# fan_control_module_0_9.net
KiCad netlist of a schematic drawn in EAGLE
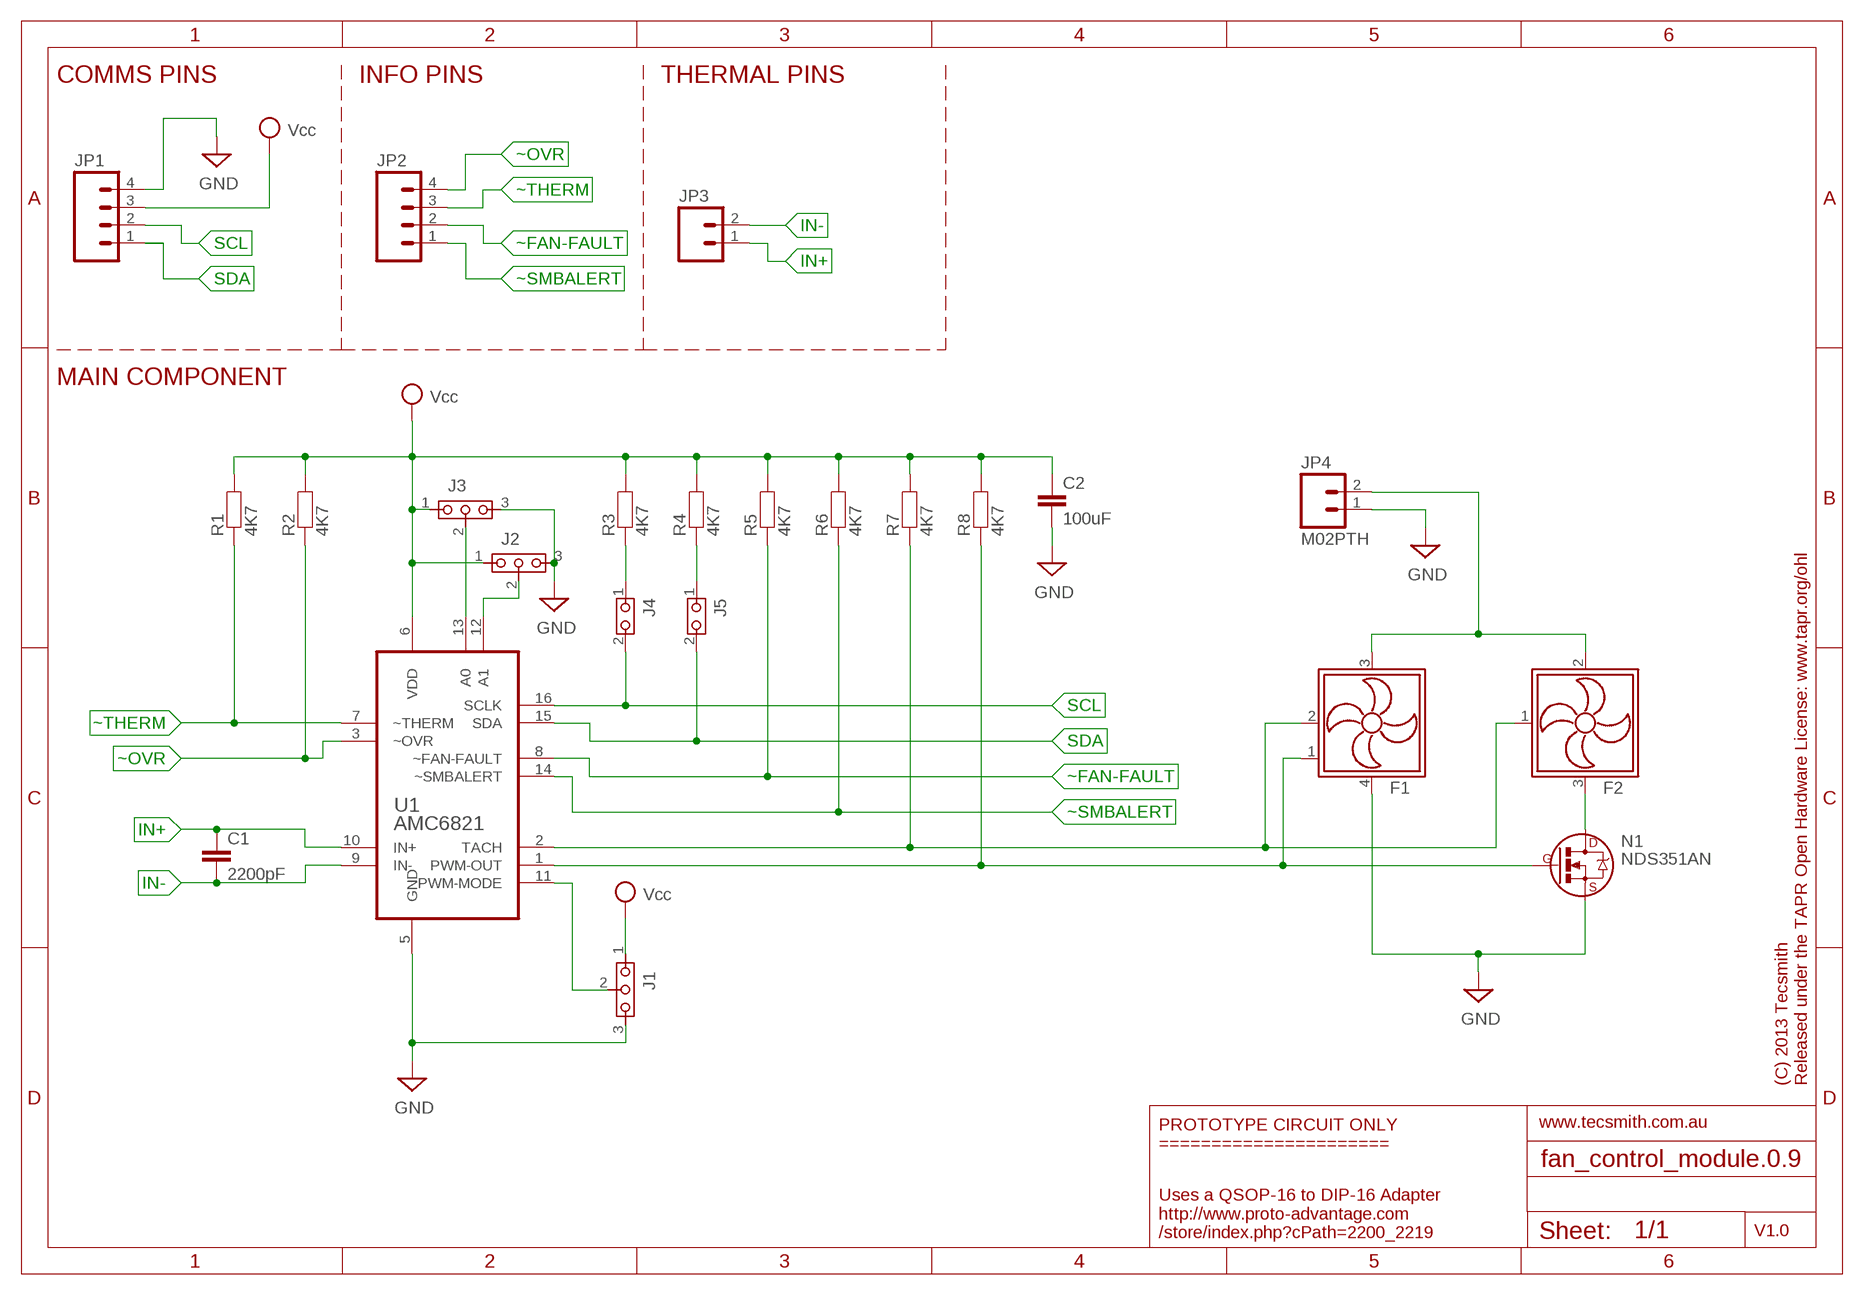
[diagram p0: schematic, sheet 1]

(export (version "E")
  (design (tool "Eeschema 10.0.6"))
  (components
    (comp (ref "C1")
      (value "2200pF")
      (footprint "eagle-import:0603")
      (libsource (lib "eagle-import") (part "CAP0603"))
    )
    (comp (ref "C2")
      (value "100uF")
      (footprint "eagle-import:0603")
      (libsource (lib "eagle-import") (part "CAP0603"))
    )
    (comp (ref "F1")
      (value "FAN_4-WIREINTEL")
      (footprint "eagle-import:47053-1000")
      (libsource (lib "eagle-import") (part "FAN_4-WIREINTEL"))
    )
    (comp (ref "F2")
      (value "FAN_3-WIRE")
      (footprint "eagle-import:22-23-2031")
      (libsource (lib "eagle-import") (part "FAN_3-WIRE"))
    )
    (comp (ref "J1")
      (value "SJ3SMD")
      (footprint "eagle-import:SJ2")
      (libsource (lib "eagle-import") (part "SJ3SMD"))
    )
    (comp (ref "J2")
      (value "SJ3SMD")
      (footprint "eagle-import:SJ2")
      (libsource (lib "eagle-import") (part "SJ3SMD"))
    )
    (comp (ref "J3")
      (value "SJ3SMD")
      (footprint "eagle-import:SJ2")
      (libsource (lib "eagle-import") (part "SJ3SMD"))
    )
    (comp (ref "J4")
      (value "SJSMD")
      (footprint "eagle-import:SJ")
      (libsource (lib "eagle-import") (part "SJSMD"))
    )
    (comp (ref "J5")
      (value "SJSMD")
      (footprint "eagle-import:SJ")
      (libsource (lib "eagle-import") (part "SJSMD"))
    )
    (comp (ref "JP1")
      (value "M04PTH")
      (footprint "eagle-import:1X04")
      (libsource (lib "eagle-import") (part "M04PTH"))
    )
    (comp (ref "JP2")
      (value "M04PTH")
      (footprint "eagle-import:1X04")
      (libsource (lib "eagle-import") (part "M04PTH"))
    )
    (comp (ref "JP3")
      (value "M02PTH")
      (footprint "eagle-import:1X02")
      (libsource (lib "eagle-import") (part "M02PTH"))
    )
    (comp (ref "JP4")
      (value "M02PTH")
      (footprint "eagle-import:1X02")
      (libsource (lib "eagle-import") (part "M02PTH"))
    )
    (comp (ref "N1")
      (value "NDS351AN")
      (footprint "eagle-import:SOT23")
      (libsource (lib "eagle-import") (part "NMOSFETGSD"))
    )
    (comp (ref "R1")
      (value "4K7")
      (footprint "eagle-import:0603")
      (libsource (lib "eagle-import") (part "RESISTOR0603"))
    )
    (comp (ref "R2")
      (value "4K7")
      (footprint "eagle-import:0603")
      (libsource (lib "eagle-import") (part "RESISTOR0603"))
    )
    (comp (ref "R3")
      (value "4K7")
      (footprint "eagle-import:0603")
      (libsource (lib "eagle-import") (part "RESISTOR0603"))
    )
    (comp (ref "R4")
      (value "4K7")
      (footprint "eagle-import:0603")
      (libsource (lib "eagle-import") (part "RESISTOR0603"))
    )
    (comp (ref "R5")
      (value "4K7")
      (footprint "eagle-import:0603")
      (libsource (lib "eagle-import") (part "RESISTOR0603"))
    )
    (comp (ref "R6")
      (value "4K7")
      (footprint "eagle-import:0603")
      (libsource (lib "eagle-import") (part "RESISTOR0603"))
    )
    (comp (ref "R7")
      (value "4K7")
      (footprint "eagle-import:0603")
      (libsource (lib "eagle-import") (part "RESISTOR0603"))
    )
    (comp (ref "R8")
      (value "4K7")
      (footprint "eagle-import:0603")
      (libsource (lib "eagle-import") (part "RESISTOR0603"))
    )
    (comp (ref "U1")
      (value "AMC6821")
      (footprint "eagle-import:QSOP-16N")
      (fields (field (name "MPN") "AMC6821SDBQ"))
      (libsource (lib "eagle-import") (part "AMC6821SDBQQSOP"))
    )
  )
  (nets
    (net (code "1") (name "/VFAN") (class "Default")
      (node (ref "F1") (pin "3") (pinfunction "PWR_3") (pintype "power_in"))
      (node (ref "F2") (pin "2") (pinfunction "PWR_2") (pintype "power_in"))
      (node (ref "JP4") (pin "2") (pinfunction "2_2") (pintype "passive"))
    )
    (net (code "2") (name "/~{FAN-FAULT}") (class "Default")
      (node (ref "JP2") (pin "2") (pinfunction "2_2") (pintype "passive"))
      (node (ref "R5") (pin "1") (pinfunction "1_1") (pintype "passive"))
      (node (ref "U1") (pin "8") (pinfunction "~{FAN-FAULT}_8") (pintype "output"))
    )
    (net (code "3") (name "/~{OVR}") (class "Default")
      (node (ref "JP2") (pin "4") (pinfunction "4_4") (pintype "passive"))
      (node (ref "R2") (pin "1") (pinfunction "1_1") (pintype "passive"))
      (node (ref "U1") (pin "3") (pinfunction "~{OVR}_3") (pintype "output"))
    )
    (net (code "4") (name "/~{SMBALERT}") (class "Default")
      (node (ref "JP2") (pin "1") (pinfunction "1_1") (pintype "passive"))
      (node (ref "R6") (pin "1") (pinfunction "1_1") (pintype "passive"))
      (node (ref "U1") (pin "14") (pinfunction "~{SMBALERT}_14") (pintype "output"))
    )
    (net (code "5") (name "/~{THERM}") (class "Default")
      (node (ref "JP2") (pin "3") (pinfunction "3_3") (pintype "passive"))
      (node (ref "R1") (pin "1") (pinfunction "1_1") (pintype "passive"))
      (node (ref "U1") (pin "7") (pinfunction "~{THERM}_7") (pintype "bidirectional"))
    )
    (net (code "6") (name "GND") (class "Default")
      (node (ref "C2") (pin "2") (pinfunction "2_2") (pintype "passive"))
      (node (ref "F1") (pin "4") (pinfunction "GND_4") (pintype "output"))
      (node (ref "J1") (pin "3") (pinfunction "3_3") (pintype "passive"))
      (node (ref "J2") (pin "3") (pinfunction "3_3") (pintype "passive"))
      (node (ref "J3") (pin "3") (pinfunction "3_3") (pintype "passive"))
      (node (ref "JP1") (pin "4") (pinfunction "4_4") (pintype "passive"))
      (node (ref "JP4") (pin "1") (pinfunction "1_1") (pintype "passive"))
      (node (ref "N1") (pin "2") (pinfunction "S_2") (pintype "passive"))
      (node (ref "U1") (pin "5") (pinfunction "GND_5") (pintype "passive"))
    )
    (net (code "7") (name "IN+") (class "Default")
      (node (ref "C1") (pin "1") (pinfunction "1_1") (pintype "passive"))
      (node (ref "JP3") (pin "1") (pinfunction "1_1") (pintype "passive"))
      (node (ref "U1") (pin "10") (pinfunction "IN+_10") (pintype "input"))
    )
    (net (code "8") (name "IN-") (class "Default")
      (node (ref "C1") (pin "2") (pinfunction "2_2") (pintype "passive"))
      (node (ref "JP3") (pin "2") (pinfunction "2_2") (pintype "passive"))
      (node (ref "U1") (pin "9") (pinfunction "IN-_9") (pintype "input"))
    )
    (net (code "9") (name "Net-(F1-PWM)") (class "Default")
      (node (ref "F1") (pin "1") (pinfunction "PWM_1") (pintype "input"))
      (node (ref "N1") (pin "1") (pinfunction "G_1") (pintype "passive"))
      (node (ref "R8") (pin "1") (pinfunction "1_1") (pintype "passive"))
      (node (ref "U1") (pin "1") (pinfunction "PWM-OUT_1") (pintype "output"))
    )
    (net (code "10") (name "Net-(F1-SENSE)") (class "Default")
      (node (ref "F1") (pin "2") (pinfunction "SENSE_2") (pintype "bidirectional"))
      (node (ref "F2") (pin "1") (pinfunction "SENSE_1") (pintype "bidirectional"))
      (node (ref "R7") (pin "1") (pinfunction "1_1") (pintype "passive"))
      (node (ref "U1") (pin "2") (pinfunction "TACH_2") (pintype "input"))
    )
    (net (code "11") (name "Net-(F2-GND)") (class "Default")
      (node (ref "F2") (pin "3") (pinfunction "GND_3") (pintype "output"))
      (node (ref "N1") (pin "3") (pinfunction "D_3") (pintype "passive"))
    )
    (net (code "12") (name "Net-(J4-Pad1)") (class "Default")
      (node (ref "J4") (pin "1") (pinfunction "1_1") (pintype "passive"))
      (node (ref "R3") (pin "1") (pinfunction "1_1") (pintype "passive"))
    )
    (net (code "13") (name "Net-(J5-Pad1)") (class "Default")
      (node (ref "J5") (pin "1") (pinfunction "1_1") (pintype "passive"))
      (node (ref "R4") (pin "1") (pinfunction "1_1") (pintype "passive"))
    )
    (net (code "14") (name "Net-(U1-A0)") (class "Default")
      (node (ref "J3") (pin "2") (pinfunction "2_2") (pintype "passive"))
      (node (ref "U1") (pin "13") (pinfunction "A0_13") (pintype "input"))
    )
    (net (code "15") (name "Net-(U1-A1)") (class "Default")
      (node (ref "J2") (pin "2") (pinfunction "2_2") (pintype "passive"))
      (node (ref "U1") (pin "12") (pinfunction "A1_12") (pintype "input"))
    )
    (net (code "16") (name "Net-(U1-PWM-MODE)") (class "Default")
      (node (ref "J1") (pin "2") (pinfunction "2_2") (pintype "passive"))
      (node (ref "U1") (pin "11") (pinfunction "PWM-MODE_11") (pintype "input"))
    )
    (net (code "17") (name "SCL") (class "Default")
      (node (ref "J4") (pin "2") (pinfunction "2_2") (pintype "passive"))
      (node (ref "JP1") (pin "2") (pinfunction "2_2") (pintype "passive"))
      (node (ref "U1") (pin "16") (pinfunction "SCLK_16") (pintype "input"))
    )
    (net (code "18") (name "SDA") (class "Default")
      (node (ref "J5") (pin "2") (pinfunction "2_2") (pintype "passive"))
      (node (ref "JP1") (pin "1") (pinfunction "1_1") (pintype "passive"))
      (node (ref "U1") (pin "15") (pinfunction "SDA_15") (pintype "bidirectional"))
    )
    (net (code "19") (name "Vcc") (class "Default")
      (node (ref "C2") (pin "1") (pinfunction "1_1") (pintype "passive"))
      (node (ref "J1") (pin "1") (pinfunction "1_1") (pintype "passive"))
      (node (ref "J2") (pin "1") (pinfunction "1_1") (pintype "passive"))
      (node (ref "J3") (pin "1") (pinfunction "1_1") (pintype "passive"))
      (node (ref "JP1") (pin "3") (pinfunction "3_3") (pintype "passive"))
      (node (ref "R1") (pin "2") (pinfunction "2_2") (pintype "passive"))
      (node (ref "R2") (pin "2") (pinfunction "2_2") (pintype "passive"))
      (node (ref "R3") (pin "2") (pinfunction "2_2") (pintype "passive"))
      (node (ref "R4") (pin "2") (pinfunction "2_2") (pintype "passive"))
      (node (ref "R5") (pin "2") (pinfunction "2_2") (pintype "passive"))
      (node (ref "R6") (pin "2") (pinfunction "2_2") (pintype "passive"))
      (node (ref "R7") (pin "2") (pinfunction "2_2") (pintype "passive"))
      (node (ref "R8") (pin "2") (pinfunction "2_2") (pintype "passive"))
      (node (ref "U1") (pin "6") (pinfunction "VDD_6") (pintype "power_in"))
    )
  )
)
